# 1_3.net
KiCad netlist of a schematic drawn in EAGLE
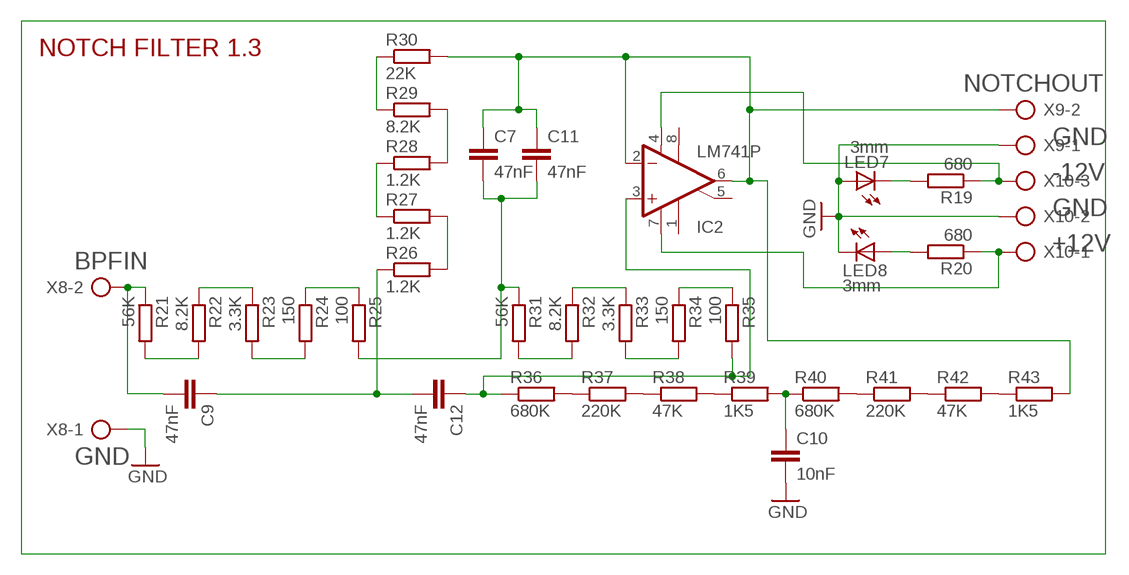
[diagram p0: schematic, sheet 1]

(export (version "E")
  (design (tool "Eeschema 10.0.6"))
  (components
    (comp (ref "C7")
      (value "47nF")
      (footprint "eagle-import:C050-025X075")
      (libsource (lib "eagle-import") (part "C-EU050-025X075"))
    )
    (comp (ref "C9")
      (value "47nF")
      (footprint "eagle-import:C050-025X075")
      (libsource (lib "eagle-import") (part "C-EU050-025X075"))
    )
    (comp (ref "C10")
      (value "10nF")
      (footprint "eagle-import:C050-025X075")
      (libsource (lib "eagle-import") (part "C-EU050-025X075"))
    )
    (comp (ref "C11")
      (value "47nF")
      (footprint "eagle-import:C050-025X075")
      (libsource (lib "eagle-import") (part "C-EU050-025X075"))
    )
    (comp (ref "C12")
      (value "47nF")
      (footprint "eagle-import:C050-025X075")
      (libsource (lib "eagle-import") (part "C-EU050-025X075"))
    )
    (comp (ref "IC2")
      (value "LM741P")
      (footprint "eagle-import:DIL08")
      (libsource (lib "eagle-import") (part "741PLM"))
    )
    (comp (ref "LED7")
      (value "3mm")
      (footprint "eagle-import:LED5MM")
      (libsource (lib "eagle-import") (part "LED5MM"))
    )
    (comp (ref "LED8")
      (value "3mm")
      (footprint "eagle-import:LED5MM")
      (libsource (lib "eagle-import") (part "LED5MM"))
    )
    (comp (ref "R19")
      (value "680")
      (footprint "eagle-import:0207_10")
      (libsource (lib "eagle-import") (part "R-EU_0207/10"))
    )
    (comp (ref "R20")
      (value "680")
      (footprint "eagle-import:0207_10")
      (libsource (lib "eagle-import") (part "R-EU_0207/10"))
    )
    (comp (ref "R21")
      (value "56K")
      (footprint "eagle-import:0207_10")
      (libsource (lib "eagle-import") (part "R-EU_0207/10"))
    )
    (comp (ref "R22")
      (value "8.2K")
      (footprint "eagle-import:0207_10")
      (libsource (lib "eagle-import") (part "R-EU_0207/10"))
    )
    (comp (ref "R23")
      (value "3.3K")
      (footprint "eagle-import:0207_10")
      (libsource (lib "eagle-import") (part "R-EU_0207/10"))
    )
    (comp (ref "R24")
      (value "150")
      (footprint "eagle-import:0207_10")
      (libsource (lib "eagle-import") (part "R-EU_0207/10"))
    )
    (comp (ref "R25")
      (value "100")
      (footprint "eagle-import:0207_10")
      (libsource (lib "eagle-import") (part "R-EU_0207/10"))
    )
    (comp (ref "R26")
      (value "1.2K")
      (footprint "eagle-import:0207_10")
      (libsource (lib "eagle-import") (part "R-EU_0207/10"))
    )
    (comp (ref "R27")
      (value "1.2K")
      (footprint "eagle-import:0207_10")
      (libsource (lib "eagle-import") (part "R-EU_0207/10"))
    )
    (comp (ref "R28")
      (value "1.2K")
      (footprint "eagle-import:0207_10")
      (libsource (lib "eagle-import") (part "R-EU_0207/10"))
    )
    (comp (ref "R29")
      (value "8.2K")
      (footprint "eagle-import:0207_10")
      (libsource (lib "eagle-import") (part "R-EU_0207/10"))
    )
    (comp (ref "R30")
      (value "22K")
      (footprint "eagle-import:0207_10")
      (libsource (lib "eagle-import") (part "R-EU_0207/10"))
    )
    (comp (ref "R31")
      (value "56K")
      (footprint "eagle-import:0207_10")
      (libsource (lib "eagle-import") (part "R-EU_0207/10"))
    )
    (comp (ref "R32")
      (value "8.2K")
      (footprint "eagle-import:0207_10")
      (libsource (lib "eagle-import") (part "R-EU_0207/10"))
    )
    (comp (ref "R33")
      (value "3.3K")
      (footprint "eagle-import:0207_10")
      (libsource (lib "eagle-import") (part "R-EU_0207/10"))
    )
    (comp (ref "R34")
      (value "150")
      (footprint "eagle-import:0207_10")
      (libsource (lib "eagle-import") (part "R-EU_0207/10"))
    )
    (comp (ref "R35")
      (value "100")
      (footprint "eagle-import:0207_10")
      (libsource (lib "eagle-import") (part "R-EU_0207/10"))
    )
    (comp (ref "R36")
      (value "680K")
      (footprint "eagle-import:0207_10")
      (libsource (lib "eagle-import") (part "R-EU_0207/10"))
    )
    (comp (ref "R37")
      (value "220K")
      (footprint "eagle-import:0207_10")
      (libsource (lib "eagle-import") (part "R-EU_0207/10"))
    )
    (comp (ref "R38")
      (value "47K")
      (footprint "eagle-import:0207_10")
      (libsource (lib "eagle-import") (part "R-EU_0207/10"))
    )
    (comp (ref "R39")
      (value "1K5")
      (footprint "eagle-import:0207_10")
      (libsource (lib "eagle-import") (part "R-EU_0207/10"))
    )
    (comp (ref "R40")
      (value "680K")
      (footprint "eagle-import:0207_10")
      (libsource (lib "eagle-import") (part "R-EU_0207/10"))
    )
    (comp (ref "R41")
      (value "220K")
      (footprint "eagle-import:0207_10")
      (libsource (lib "eagle-import") (part "R-EU_0207/10"))
    )
    (comp (ref "R42")
      (value "47K")
      (footprint "eagle-import:0207_10")
      (libsource (lib "eagle-import") (part "R-EU_0207/10"))
    )
    (comp (ref "R43")
      (value "1K5")
      (footprint "eagle-import:0207_10")
      (libsource (lib "eagle-import") (part "R-EU_0207/10"))
    )
    (comp (ref "X8")
      (value "AK500/2-H")
      (footprint "eagle-import:AK500_2-H")
      (libsource (lib "eagle-import") (part "AK500/2-H"))
    )
    (comp (ref "X9")
      (value "AK500/2-H")
      (footprint "eagle-import:AK500_2-H")
      (libsource (lib "eagle-import") (part "AK500/2-H"))
    )
    (comp (ref "X10")
      (value "AK500/3-H")
      (footprint "eagle-import:AK500_3-H")
      (libsource (lib "eagle-import") (part "AK500/3-H"))
    )
  )
  (nets
    (net (code "1") (name "/+12V") (class "Default")
      (node (ref "IC2") (pin "7") (pinfunction "V+_7") (pintype "power_in"))
      (node (ref "R20") (pin "1") (pinfunction "1_1") (pintype "passive"))
      (node (ref "X10") (pin "1") (pinfunction "KL_1") (pintype "passive"))
    )
    (net (code "2") (name "/-12V") (class "Default")
      (node (ref "IC2") (pin "4") (pinfunction "V-_4") (pintype "power_in"))
      (node (ref "R19") (pin "1") (pinfunction "1_1") (pintype "passive"))
      (node (ref "X10") (pin "3") (pinfunction "KL_3") (pintype "passive"))
    )
    (net (code "3") (name "/BPFIN") (class "Default")
      (node (ref "C9") (pin "2") (pinfunction "2_2") (pintype "passive"))
      (node (ref "R21") (pin "1") (pinfunction "1_1") (pintype "passive"))
      (node (ref "X8") (pin "2") (pinfunction "KL_2") (pintype "passive"))
    )
    (net (code "4") (name "/NOTCHOUT") (class "Default")
      (node (ref "C11") (pin "1") (pinfunction "1_1") (pintype "passive"))
      (node (ref "C7") (pin "1") (pinfunction "1_1") (pintype "passive"))
      (node (ref "IC2") (pin "2") (pinfunction "-IN_2") (pintype "input"))
      (node (ref "IC2") (pin "6") (pinfunction "OUT_6") (pintype "output"))
      (node (ref "R30") (pin "2") (pinfunction "2_2") (pintype "passive"))
      (node (ref "R43") (pin "2") (pinfunction "2_2") (pintype "passive"))
      (node (ref "X9") (pin "2") (pinfunction "KL_2") (pintype "passive"))
    )
    (net (code "5") (name "GND") (class "Default")
      (node (ref "C10") (pin "2") (pinfunction "2_2") (pintype "passive"))
      (node (ref "LED7") (pin "A") (pinfunction "A_A") (pintype "passive"))
      (node (ref "LED8") (pin "K") (pinfunction "C_K") (pintype "passive"))
      (node (ref "X10") (pin "2") (pinfunction "KL_2") (pintype "passive"))
      (node (ref "X8") (pin "1") (pinfunction "KL_1") (pintype "passive"))
      (node (ref "X9") (pin "1") (pinfunction "KL_1") (pintype "passive"))
    )
    (net (code "6") (name "Net-(C10-Pad1)") (class "Default")
      (node (ref "C10") (pin "1") (pinfunction "1_1") (pintype "passive"))
      (node (ref "R39") (pin "2") (pinfunction "2_2") (pintype "passive"))
      (node (ref "R40") (pin "1") (pinfunction "1_1") (pintype "passive"))
    )
    (net (code "7") (name "Net-(C11-Pad2)") (class "Default")
      (node (ref "C11") (pin "2") (pinfunction "2_2") (pintype "passive"))
      (node (ref "C7") (pin "2") (pinfunction "2_2") (pintype "passive"))
      (node (ref "R25") (pin "2") (pinfunction "2_2") (pintype "passive"))
      (node (ref "R31") (pin "1") (pinfunction "1_1") (pintype "passive"))
    )
    (net (code "8") (name "Net-(C12-Pad2)") (class "Default")
      (node (ref "C12") (pin "2") (pinfunction "2_2") (pintype "passive"))
      (node (ref "C9") (pin "1") (pinfunction "1_1") (pintype "passive"))
      (node (ref "R26") (pin "1") (pinfunction "1_1") (pintype "passive"))
    )
    (net (code "9") (name "Net-(IC2-+IN)") (class "Default")
      (node (ref "C12") (pin "1") (pinfunction "1_1") (pintype "passive"))
      (node (ref "IC2") (pin "3") (pinfunction "+IN_3") (pintype "input"))
      (node (ref "R35") (pin "2") (pinfunction "2_2") (pintype "passive"))
      (node (ref "R36") (pin "1") (pinfunction "1_1") (pintype "passive"))
    )
    (net (code "10") (name "Net-(LED7-C)") (class "Default")
      (node (ref "LED7") (pin "K") (pinfunction "C_K") (pintype "passive"))
      (node (ref "R19") (pin "2") (pinfunction "2_2") (pintype "passive"))
    )
    (net (code "11") (name "Net-(LED8-PadA)") (class "Default")
      (node (ref "LED8") (pin "A") (pinfunction "A_A") (pintype "passive"))
      (node (ref "R20") (pin "2") (pinfunction "2_2") (pintype "passive"))
    )
    (net (code "12") (name "Net-(R21-Pad2)") (class "Default")
      (node (ref "R21") (pin "2") (pinfunction "2_2") (pintype "passive"))
      (node (ref "R22") (pin "2") (pinfunction "2_2") (pintype "passive"))
    )
    (net (code "13") (name "Net-(R22-Pad1)") (class "Default")
      (node (ref "R22") (pin "1") (pinfunction "1_1") (pintype "passive"))
      (node (ref "R23") (pin "1") (pinfunction "1_1") (pintype "passive"))
    )
    (net (code "14") (name "Net-(R23-Pad2)") (class "Default")
      (node (ref "R23") (pin "2") (pinfunction "2_2") (pintype "passive"))
      (node (ref "R24") (pin "2") (pinfunction "2_2") (pintype "passive"))
    )
    (net (code "15") (name "Net-(R24-Pad1)") (class "Default")
      (node (ref "R24") (pin "1") (pinfunction "1_1") (pintype "passive"))
      (node (ref "R25") (pin "1") (pinfunction "1_1") (pintype "passive"))
    )
    (net (code "16") (name "Net-(R26-Pad2)") (class "Default")
      (node (ref "R26") (pin "2") (pinfunction "2_2") (pintype "passive"))
      (node (ref "R27") (pin "2") (pinfunction "2_2") (pintype "passive"))
    )
    (net (code "17") (name "Net-(R27-Pad1)") (class "Default")
      (node (ref "R27") (pin "1") (pinfunction "1_1") (pintype "passive"))
      (node (ref "R28") (pin "1") (pinfunction "1_1") (pintype "passive"))
    )
    (net (code "18") (name "Net-(R28-Pad2)") (class "Default")
      (node (ref "R28") (pin "2") (pinfunction "2_2") (pintype "passive"))
      (node (ref "R29") (pin "2") (pinfunction "2_2") (pintype "passive"))
    )
    (net (code "19") (name "Net-(R29-Pad1)") (class "Default")
      (node (ref "R29") (pin "1") (pinfunction "1_1") (pintype "passive"))
      (node (ref "R30") (pin "1") (pinfunction "1_1") (pintype "passive"))
    )
    (net (code "20") (name "Net-(R31-Pad2)") (class "Default")
      (node (ref "R31") (pin "2") (pinfunction "2_2") (pintype "passive"))
      (node (ref "R32") (pin "2") (pinfunction "2_2") (pintype "passive"))
    )
    (net (code "21") (name "Net-(R32-Pad1)") (class "Default")
      (node (ref "R32") (pin "1") (pinfunction "1_1") (pintype "passive"))
      (node (ref "R33") (pin "1") (pinfunction "1_1") (pintype "passive"))
    )
    (net (code "22") (name "Net-(R33-Pad2)") (class "Default")
      (node (ref "R33") (pin "2") (pinfunction "2_2") (pintype "passive"))
      (node (ref "R34") (pin "2") (pinfunction "2_2") (pintype "passive"))
    )
    (net (code "23") (name "Net-(R34-Pad1)") (class "Default")
      (node (ref "R34") (pin "1") (pinfunction "1_1") (pintype "passive"))
      (node (ref "R35") (pin "1") (pinfunction "1_1") (pintype "passive"))
    )
    (net (code "24") (name "Net-(R36-Pad2)") (class "Default")
      (node (ref "R36") (pin "2") (pinfunction "2_2") (pintype "passive"))
      (node (ref "R37") (pin "1") (pinfunction "1_1") (pintype "passive"))
    )
    (net (code "25") (name "Net-(R37-Pad2)") (class "Default")
      (node (ref "R37") (pin "2") (pinfunction "2_2") (pintype "passive"))
      (node (ref "R38") (pin "1") (pinfunction "1_1") (pintype "passive"))
    )
    (net (code "26") (name "Net-(R38-Pad2)") (class "Default")
      (node (ref "R38") (pin "2") (pinfunction "2_2") (pintype "passive"))
      (node (ref "R39") (pin "1") (pinfunction "1_1") (pintype "passive"))
    )
    (net (code "27") (name "Net-(R40-Pad2)") (class "Default")
      (node (ref "R40") (pin "2") (pinfunction "2_2") (pintype "passive"))
      (node (ref "R41") (pin "1") (pinfunction "1_1") (pintype "passive"))
    )
    (net (code "28") (name "Net-(R41-Pad2)") (class "Default")
      (node (ref "R41") (pin "2") (pinfunction "2_2") (pintype "passive"))
      (node (ref "R42") (pin "1") (pinfunction "1_1") (pintype "passive"))
    )
    (net (code "29") (name "Net-(R42-Pad2)") (class "Default")
      (node (ref "R42") (pin "2") (pinfunction "2_2") (pintype "passive"))
      (node (ref "R43") (pin "1") (pinfunction "1_1") (pintype "passive"))
    )
    (net (code "30") (name "unconnected-(IC2-ON1-Pad1)") (class "Default")
      (node (ref "IC2") (pin "1") (pinfunction "ON1_1") (pintype "passive"))
    )
    (net (code "31") (name "unconnected-(IC2-ON2-Pad5)") (class "Default")
      (node (ref "IC2") (pin "5") (pinfunction "ON2_5") (pintype "passive"))
    )
    (net (code "32") (name "unconnected-(IC2-OPT-Pad8)") (class "Default")
      (node (ref "IC2") (pin "8") (pinfunction "OPT_8") (pintype "passive"))
    )
  )
)
